# NCS_Wireless_Indicator_power_supply.net
KiCad netlist of a schematic drawn in Altium Designer
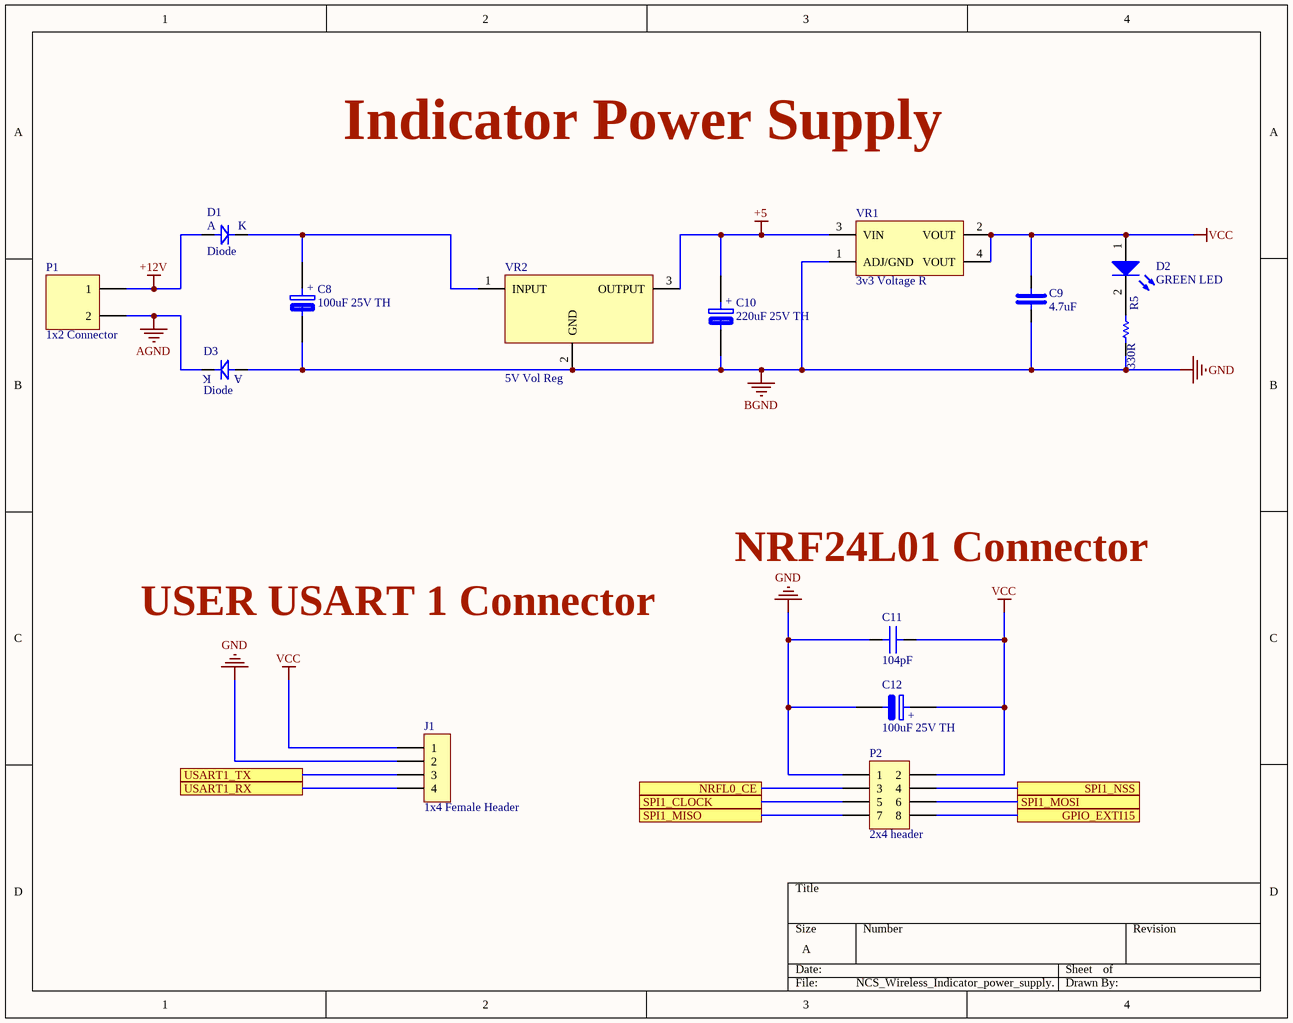
[diagram p0: NCS_Wireless_Indicator_power_supply.SchDoc]

(export (version "E")
  (design (tool "Eeschema 10.0.6"))
  (components
    (comp (ref "C8")
      (value "100uF 25V TH")
      (footprint "100uF 25V TH")
      (description "WCAP-ATG8 Aluminum Electrolytic Capacitors")
      (fields
        (field (name "MANUFACTURER") "Wurth Electronics")
        (field (name "MANUFACTURER PART NUMBER") "860010473007")
      )
      (libsource (lib "schlib") (part "860010473007"))
    )
    (comp (ref "C9")
      (value "4.7uF")
      (footprint "C0805C209D3HACTU_2pF")
      (description "Multilayer Ceramic Capacitor, 4.7 uF, 25 V, ï¿½ 10%, X5R, 0805 [2012 Metric]")
      (fields
        (field (name "MANUFACTURER") "KEMET")
        (field (name "MANUFACTURER PART NUMBER") "C0805C475K3PACTU")
      )
      (libsource (lib "schlib") (part "C0805C475K3PACTU"))
    )
    (comp (ref "C10")
      (value "220uF 25V TH")
      (footprint "100uF 25V TH")
      (description "WCAP-ATG8 Aluminum Electrolytic Capacitors")
      (fields
        (field (name "MANUFACTURER") "Wurth Electronics")
        (field (name "MANUFACTURER PART NUMBER") "860010473007")
      )
      (libsource (lib "schlib") (part "860010473007"))
    )
    (comp (ref "C11")
      (value "104pF")
      (footprint "C0805C471K3RACTU_470pF")
      (description "Capacitor, Ceramic, 470pF, 25VDC, 10-% Tol, 10+% Tol, X7R-TC Code, -15, 15%-TC RoHS Compliant: Yes")
      (fields
        (field (name "MANUFACTURER") "KEMET")
        (field (name "MANUFACTURER PART NUMBER") "C0805C471K3RACTU")
      )
      (libsource (lib "schlib") (part "C0805C471K3RACTU"))
    )
    (comp (ref "C12")
      (value "100uF 25V TH")
      (footprint "100uF 25V TH")
      (description "WCAP-ATG8 Aluminum Electrolytic Capacitors")
      (fields
        (field (name "MANUFACTURER") "Wurth Electronics")
        (field (name "MANUFACTURER PART NUMBER") "860010473007")
      )
      (libsource (lib "schlib") (part "860010473007"))
    )
    (comp (ref "D1")
      (value "Diode")
      (footprint "CRS06(TE85L,Q,M)_DIODE")
      (description "Diode Schottky 20V 1A 2-Pin S-FLAT T/R / DIODE SCHOTTKY 20V 1A SFLAT")
      (fields
        (field (name "MANUFACTURER") "Toshiba")
        (field (name "MANUFACTURER PART NUMBER") "CRS06(TE85L,Q,M)")
      )
      (libsource (lib "schlib") (part "CRS06(TE85L,Q,M)"))
    )
    (comp (ref "D2")
      (value "GREEN LED")
      (footprint "LTST-C171GKT_GREEN")
      (description "LED Low-Power Uni-Color Green 565nm 2.1V 2-Pin Chip LED T/R")
      (fields
        (field (name "MANUFACTURER") "Vishay Lite-On")
        (field (name "MANUFACTURER PART NUMBER") "LTST-C171GKT")
      )
      (libsource (lib "schlib") (part "LTST-C171GKT"))
    )
    (comp (ref "D3")
      (value "Diode")
      (footprint "CRS06(TE85L,Q,M)_DIODE")
      (description "Diode Schottky 20V 1A 2-Pin S-FLAT T/R / DIODE SCHOTTKY 20V 1A SFLAT")
      (fields
        (field (name "MANUFACTURER") "Toshiba")
        (field (name "MANUFACTURER PART NUMBER") "CRS06(TE85L,Q,M)")
      )
      (libsource (lib "schlib") (part "CRS06(TE85L,Q,M)"))
    )
    (comp (ref "J1")
      (value "1x4 Female Header")
      (footprint "1x4 Female Header")
      (description "Female, 4 C, Straight, .100\"CC; 3.20mm Tail, No Mounting; PBT, Phos. Bronze, 105 C")
      (fields
        (field (name "MANUFACTURER") "Sullins")
        (field (name "MANUFACTURER PART NUMBER") "PPPC041LFBN-RC")
      )
      (libsource (lib "schlib") (part "PPPC041LFBN-RC"))
    )
    (comp (ref "P1")
      (value "1x2 Connector")
      (footprint "1x2 Connector")
      (description "2~24 Poles, Screw Type, Horizontal, 5.08 Pitch, 26~14 (AWG), Terminal Block Connector")
      (fields (field (name "MANUFACTURER") "CUI") (field (name "MANUFACTURER PART NUMBER") "TB006-508-02BE"))
      (libsource (lib "schlib") (part "TB006-508-02BE"))
    )
    (comp (ref "P2")
      (value "2x4 header")
      (footprint "2x4 header")
      (description "Header Connector, Pcb Mnt, 8 Contacts, Skt, 0.1 Pitch, Pc Tail Terminal, Locking")
      (fields
        (field (name "MANUFACTURER") "Sullins")
        (field (name "MANUFACTURER PART NUMBER") "PPTC042LFBN-RC")
      )
      (libsource (lib "schlib") (part "PPTC042LFBN-RC"))
    )
    (comp (ref "R5")
      (value "330R")
      (footprint "RC0805FR-7W330RL")
      (description "Res Thick Film 0805 330 Ohm 1% 0.25W(1/4W) ±200ppm/C Pad SMD T/R")
      (fields
        (field (name "MANUFACTURER") "Yageo")
        (field (name "MANUFACTURER PART NUMBER") "RC0805FR-7W330RL")
      )
      (libsource (lib "schlib") (part "RC0805FR-7W330RL"))
    )
    (comp (ref "VR1")
      (value "3v3 Voltage R")
      (footprint "SAMS1117-33-4N")
      (libsource (lib "NCS_Wireless_Bed_Unit") (part "AMS1117-33-3.3V"))
    )
    (comp (ref "VR2")
      (value "5V Vol Reg")
      (footprint "5V Vol Reg DIP")
      (description "Voltage Regulator; linear; fixed; Vout: 5V; Vin: 7-35V; Vd: 2V; 2%; 1A; 0+150 deg.C; THT; TO220")
      (fields
        (field (name "MANUFACTURER") "STMicroelectronics")
        (field (name "MANUFACTURER PART NUMBER") "L7805CV")
      )
      (libsource (lib "schlib") (part "L7805CV"))
    )
  )
  (nets
    (net (code "1") (name "+5") (class "Default")
      (node (ref "C10") (pin "1") (pinfunction "1_1") (pintype "passive"))
      (node (ref "VR1") (pin "3") (pinfunction "VIN_3") (pintype "passive"))
      (node (ref "VR2") (pin "3") (pinfunction "OUTPUT_3") (pintype "passive"))
    )
    (net (code "2") (name "+12V") (class "Default")
      (node (ref "D1") (pin "1") (pinfunction "1_1") (pintype "passive"))
      (node (ref "P1") (pin "1") (pinfunction "1_1") (pintype "passive"))
    )
    (net (code "3") (name "/GPIO_EXTI15") (class "Default")
      (node (ref "P2") (pin "8") (pinfunction "8_8") (pintype "passive"))
    )
    (net (code "4") (name "/NRFL0_CE") (class "Default")
      (node (ref "P2") (pin "3") (pinfunction "3_3") (pintype "passive"))
    )
    (net (code "5") (name "/SPI1_CLOCK") (class "Default")
      (node (ref "P2") (pin "5") (pinfunction "5_5") (pintype "passive"))
    )
    (net (code "6") (name "/SPI1_MISO") (class "Default")
      (node (ref "P2") (pin "7") (pinfunction "7_7") (pintype "passive"))
    )
    (net (code "7") (name "/SPI1_MOSI") (class "Default")
      (node (ref "P2") (pin "6") (pinfunction "6_6") (pintype "passive"))
    )
    (net (code "8") (name "/SPI1_NSS") (class "Default")
      (node (ref "P2") (pin "4") (pinfunction "4_4") (pintype "passive"))
    )
    (net (code "9") (name "/USART1_RX") (class "Default")
      (node (ref "J1") (pin "4") (pinfunction "4_4") (pintype "passive"))
    )
    (net (code "10") (name "/USART1_TX") (class "Default")
      (node (ref "J1") (pin "3") (pinfunction "3_3") (pintype "passive"))
    )
    (net (code "11") (name "AGND") (class "Default")
      (node (ref "D3") (pin "2") (pinfunction "2_2") (pintype "passive"))
      (node (ref "P1") (pin "2") (pinfunction "2_2") (pintype "passive"))
    )
    (net (code "12") (name "BGND") (class "Default")
      (node (ref "C10") (pin "2") (pinfunction "2_2") (pintype "passive"))
      (node (ref "C11") (pin "1") (pinfunction "1_1") (pintype "passive"))
      (node (ref "C12") (pin "2") (pinfunction "2_2") (pintype "passive"))
      (node (ref "C8") (pin "2") (pinfunction "2_2") (pintype "passive"))
      (node (ref "C9") (pin "1") (pinfunction "1_1") (pintype "passive"))
      (node (ref "D3") (pin "1") (pinfunction "1_1") (pintype "passive"))
      (node (ref "J1") (pin "2") (pinfunction "2_2") (pintype "passive"))
      (node (ref "P2") (pin "1") (pinfunction "1_1") (pintype "passive"))
      (node (ref "R5") (pin "1") (pinfunction "1_1") (pintype "passive"))
      (node (ref "VR1") (pin "1") (pinfunction "ADJ/GND_1") (pintype "passive"))
      (node (ref "VR2") (pin "2") (pinfunction "GND_2") (pintype "passive"))
    )
    (net (code "13") (name "Net-(D2-K)") (class "Default")
      (node (ref "D2") (pin "2") (pinfunction "K_2") (pintype "passive"))
      (node (ref "R5") (pin "2") (pinfunction "2_2") (pintype "passive"))
    )
    (net (code "14") (name "Net-(VR2-INPUT)") (class "Default")
      (node (ref "C8") (pin "1") (pinfunction "1_1") (pintype "passive"))
      (node (ref "D1") (pin "2") (pinfunction "2_2") (pintype "passive"))
      (node (ref "VR2") (pin "1") (pinfunction "INPUT_1") (pintype "passive"))
    )
    (net (code "15") (name "VCC") (class "Default")
      (node (ref "C11") (pin "2") (pinfunction "2_2") (pintype "passive"))
      (node (ref "C12") (pin "1") (pinfunction "1_1") (pintype "passive"))
      (node (ref "C9") (pin "2") (pinfunction "2_2") (pintype "passive"))
      (node (ref "D2") (pin "1") (pinfunction "A_1") (pintype "passive"))
      (node (ref "J1") (pin "1") (pinfunction "1_1") (pintype "passive"))
      (node (ref "P2") (pin "2") (pinfunction "2_2") (pintype "passive"))
      (node (ref "VR1") (pin "2") (pinfunction "VOUT_2") (pintype "passive"))
      (node (ref "VR1") (pin "4") (pinfunction "VOUT_4") (pintype "passive"))
    )
  )
)
